# Driver.net
KiCad netlist of a schematic drawn in EAGLE
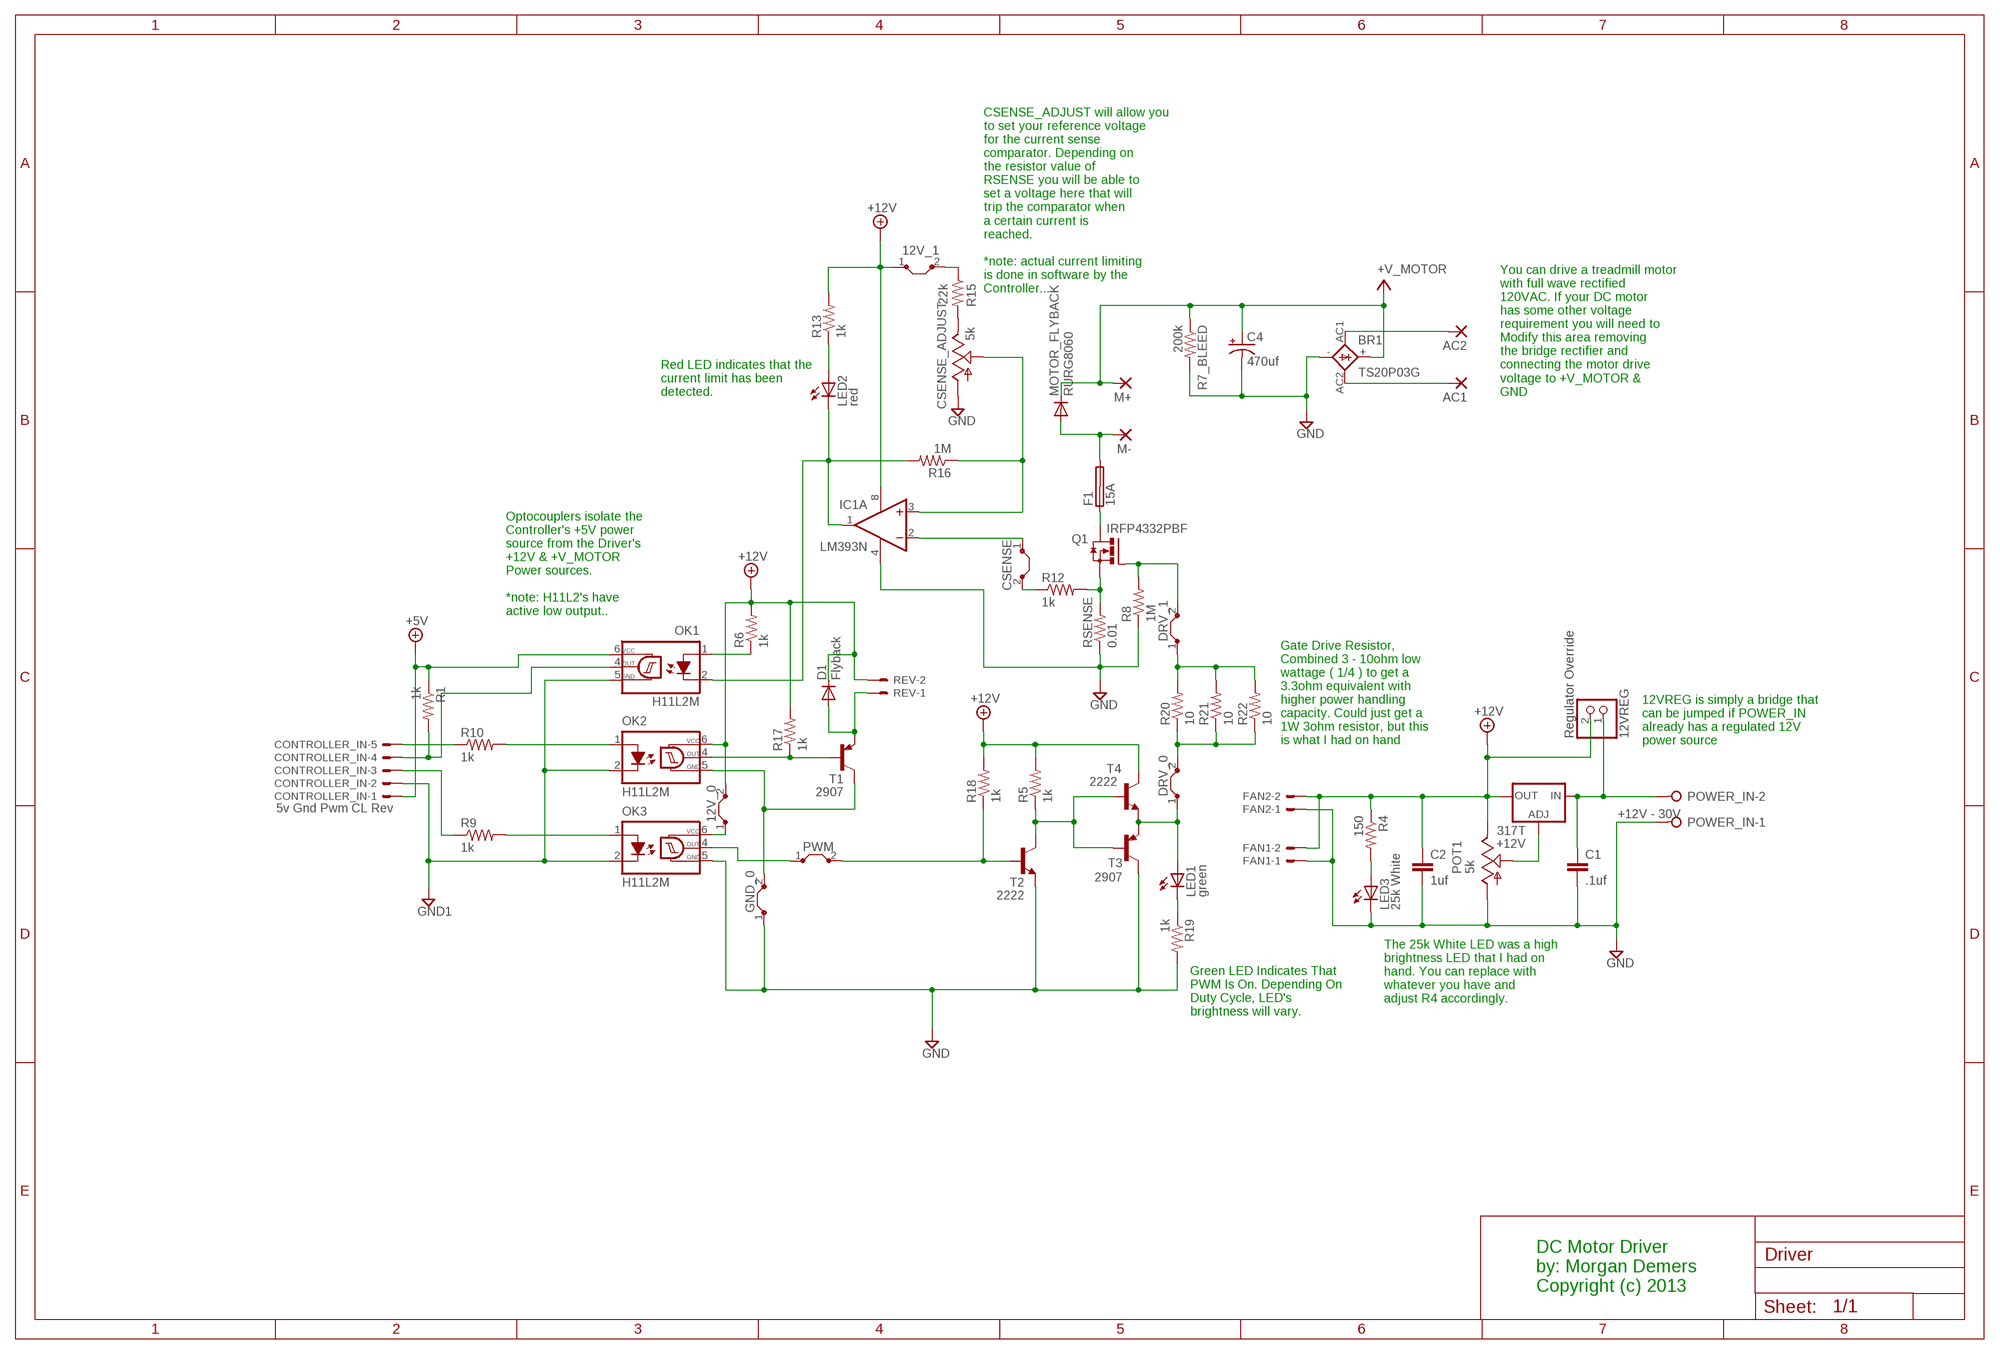
[diagram p0: schematic, sheet 1]

(export (version "E")
  (design (tool "Eeschema 10.0.6"))
  (components
    (comp (ref "12VREG")
      (value "Regulator Override")
      (footprint "eagle-import:1X02")
      (libsource (lib "eagle-import") (part "PINHD-1X2"))
    )
    (comp (ref "12V_0")
      (value "J10MM")
      (footprint "eagle-import:10")
      (libsource (lib "eagle-import") (part "J10MM"))
    )
    (comp (ref "12V_1")
      (value "J5MM")
      (footprint "eagle-import:05")
      (libsource (lib "eagle-import") (part "J5MM"))
    )
    (comp (ref "317T")
      (value "+12V")
      (footprint "eagle-import:317TS")
      (libsource (lib "eagle-import") (part "LM317TS"))
    )
    (comp (ref "AC1")
      (value "WIREPAD4,16O1,6")
      (footprint "eagle-import:4,16O1,6")
      (libsource (lib "eagle-import") (part "WIREPAD4,16O1,6"))
    )
    (comp (ref "AC2")
      (value "WIREPAD4,16O1,6")
      (footprint "eagle-import:4,16O1,6")
      (libsource (lib "eagle-import") (part "WIREPAD4,16O1,6"))
    )
    (comp (ref "BR1")
      (value "TS20P03G")
      (footprint "eagle-import:FB32")
      (libsource (lib "eagle-import") (part "FB32"))
    )
    (comp (ref "C1")
      (value ".1uf")
      (footprint "eagle-import:C2.5-3")
      (libsource (lib "eagle-import") (part "C2,5-3"))
    )
    (comp (ref "C2")
      (value "1uf")
      (footprint "eagle-import:C2.5-3")
      (libsource (lib "eagle-import") (part "C2,5-3"))
    )
    (comp (ref "C4")
      (value "470uf")
      (footprint "eagle-import:EB22,5D")
      (libsource (lib "eagle-import") (part "CPOL-USE10-22.5"))
    )
    (comp (ref "CONTROLLER_IN")
      (value "5v Gnd Pwm CL Rev")
      (footprint "eagle-import:22-23-2051")
      (fields (field (name "MF") "MOLEX") (field (name "MPN") "22-23-2051"))
      (libsource (lib "eagle-import") (part "22-23-2051"))
    )
    (comp (ref "CSENSE")
      (value "J7MM")
      (footprint "eagle-import:07")
      (libsource (lib "eagle-import") (part "J7MM"))
    )
    (comp (ref "CSENSE_ADJUST")
      (value "5k")
      (footprint "eagle-import:B25P")
      (libsource (lib "eagle-import") (part "TRIM_US-B25P"))
    )
    (comp (ref "D1")
      (value "Flyback")
      (footprint "eagle-import:D-2.5")
      (libsource (lib "eagle-import") (part "DIODE-D-2.5"))
    )
    (comp (ref "DRV_0")
      (value "J5MM")
      (footprint "eagle-import:05")
      (libsource (lib "eagle-import") (part "J5MM"))
    )
    (comp (ref "DRV_1")
      (value "J12MM")
      (footprint "eagle-import:12")
      (libsource (lib "eagle-import") (part "J12MM"))
    )
    (comp (ref "F1")
      (value "15A")
      (footprint "eagle-import:SHK20L")
      (libsource (lib "eagle-import") (part "SHK20L"))
    )
    (comp (ref "FAN1")
      (value "22-23-2021")
      (footprint "eagle-import:22-23-2021")
      (fields (field (name "MF") "MOLEX"))
      (libsource (lib "eagle-import") (part "22-23-2021"))
    )
    (comp (ref "FAN2")
      (value "22-23-2021")
      (footprint "eagle-import:22-23-2021")
      (fields (field (name "MF") "MOLEX"))
      (libsource (lib "eagle-import") (part "22-23-2021"))
    )
    (comp (ref "GND_0")
      (value "J7MM")
      (footprint "eagle-import:07")
      (libsource (lib "eagle-import") (part "J7MM"))
    )
    (comp (ref "IC1")
      (value "LM393N")
      (footprint "eagle-import:DIL08")
      (libsource (lib "eagle-import") (part "LM393N"))
    )
    (comp (ref "LED1")
      (value "green")
      (footprint "eagle-import:LED3MM")
      (libsource (lib "eagle-import") (part "LED3MM"))
    )
    (comp (ref "LED2")
      (value "red")
      (footprint "eagle-import:LED3MM")
      (libsource (lib "eagle-import") (part "LED3MM"))
    )
    (comp (ref "LED3")
      (value "25k White")
      (footprint "eagle-import:LED3MM")
      (libsource (lib "eagle-import") (part "LED3MM"))
    )
    (comp (ref "M+")
      (value "WIREPAD4,16O1,6")
      (footprint "eagle-import:4,16O1,6")
      (libsource (lib "eagle-import") (part "WIREPAD4,16O1,6"))
    )
    (comp (ref "M-")
      (value "WIREPAD4,16O1,6")
      (footprint "eagle-import:4,16O1,6")
      (libsource (lib "eagle-import") (part "WIREPAD4,16O1,6"))
    )
    (comp (ref "MOTOR_FLYBACK")
      (value "RURG8060")
      (footprint "eagle-import:TO220ACS")
      (libsource (lib "eagle-import") (part "DIODE-TO220V"))
    )
    (comp (ref "OK1")
      (value "H11L2M")
      (footprint "eagle-import:DIL06")
      (fields (field (name "MF") "FAIRCHILD SEMICONDUCTOR"))
      (libsource (lib "eagle-import") (part "H11LM2"))
    )
    (comp (ref "OK2")
      (value "H11L2M")
      (footprint "eagle-import:DIL06")
      (fields (field (name "MF") "FAIRCHILD SEMICONDUCTOR"))
      (libsource (lib "eagle-import") (part "H11LM2"))
    )
    (comp (ref "OK3")
      (value "H11L2M")
      (footprint "eagle-import:DIL06")
      (fields (field (name "MF") "FAIRCHILD SEMICONDUCTOR"))
      (libsource (lib "eagle-import") (part "H11LM2"))
    )
    (comp (ref "POT1")
      (value "5k")
      (footprint "eagle-import:B25P")
      (libsource (lib "eagle-import") (part "TRIM_US-B25P"))
    )
    (comp (ref "POWER_IN")
      (value "+12V - 30V")
      (footprint "eagle-import:W237-132")
      (libsource (lib "eagle-import") (part "W237-02P"))
    )
    (comp (ref "PWM")
      (value "J5MM")
      (footprint "eagle-import:05")
      (libsource (lib "eagle-import") (part "J5MM"))
    )
    (comp (ref "Q1")
      (value "IRFP4332PBF")
      (footprint "eagle-import:TO247BV")
      (libsource (lib "eagle-import") (part "IRFP240"))
    )
    (comp (ref "R1")
      (value "1k")
      (footprint "eagle-import:0204_7")
      (libsource (lib "eagle-import") (part "R-US_0204/7"))
    )
    (comp (ref "R4")
      (value "150")
      (footprint "eagle-import:0204V")
      (libsource (lib "eagle-import") (part "R-US_0204/2V"))
    )
    (comp (ref "R5")
      (value "1k")
      (footprint "eagle-import:0204V")
      (libsource (lib "eagle-import") (part "R-US_0204/2V"))
    )
    (comp (ref "R6")
      (value "1k")
      (footprint "eagle-import:0204V")
      (libsource (lib "eagle-import") (part "R-US_0204/2V"))
    )
    (comp (ref "R7_BLEED")
      (value "200k")
      (footprint "eagle-import:0207_10")
      (libsource (lib "eagle-import") (part "R-US_0207/10"))
    )
    (comp (ref "R8")
      (value "1M")
      (footprint "eagle-import:0204V")
      (libsource (lib "eagle-import") (part "R-US_0204/2V"))
    )
    (comp (ref "R9")
      (value "1k")
      (footprint "eagle-import:0204V")
      (libsource (lib "eagle-import") (part "R-US_0204/2V"))
    )
    (comp (ref "R10")
      (value "1k")
      (footprint "eagle-import:0204V")
      (libsource (lib "eagle-import") (part "R-US_0204/2V"))
    )
    (comp (ref "R12")
      (value "1k")
      (footprint "eagle-import:0204V")
      (libsource (lib "eagle-import") (part "R-US_0204/2V"))
    )
    (comp (ref "R13")
      (value "1k")
      (footprint "eagle-import:0204V")
      (libsource (lib "eagle-import") (part "R-US_0204/2V"))
    )
    (comp (ref "R15")
      (value "22k")
      (footprint "eagle-import:0204V")
      (libsource (lib "eagle-import") (part "R-US_0204/2V"))
    )
    (comp (ref "R16")
      (value "1M")
      (footprint "eagle-import:0204_5")
      (libsource (lib "eagle-import") (part "R-US_0204/5"))
    )
    (comp (ref "R17")
      (value "1k")
      (footprint "eagle-import:0204_5")
      (libsource (lib "eagle-import") (part "R-US_0204/5"))
    )
    (comp (ref "R18")
      (value "1k")
      (footprint "eagle-import:0204_7")
      (libsource (lib "eagle-import") (part "R-US_0204/7"))
    )
    (comp (ref "R19")
      (value "1k")
      (footprint "eagle-import:0204V")
      (libsource (lib "eagle-import") (part "R-US_0204/2V"))
    )
    (comp (ref "R20")
      (value "10")
      (footprint "eagle-import:0204V")
      (libsource (lib "eagle-import") (part "R-US_0204/2V"))
    )
    (comp (ref "R21")
      (value "10")
      (footprint "eagle-import:0204V")
      (libsource (lib "eagle-import") (part "R-US_0204/2V"))
    )
    (comp (ref "R22")
      (value "10")
      (footprint "eagle-import:0204V")
      (libsource (lib "eagle-import") (part "R-US_0204/2V"))
    )
    (comp (ref "REV")
      (value "22-23-2021")
      (footprint "eagle-import:22-23-2021")
      (fields (field (name "MF") "MOLEX"))
      (libsource (lib "eagle-import") (part "22-23-2021"))
    )
    (comp (ref "RSENSE")
      (value "0.01")
      (footprint "eagle-import:0204V")
      (libsource (lib "eagle-import") (part "R-US_0204/2V"))
    )
    (comp (ref "T1")
      (value "2907")
      (footprint "eagle-import:TO92-CBE")
      (libsource (lib "eagle-import") (part "MPSA56"))
    )
    (comp (ref "T2")
      (value "2222")
      (footprint "eagle-import:TO92-EBC")
      (libsource (lib "eagle-import") (part "-NPN-TO92-EBC"))
    )
    (comp (ref "T3")
      (value "2907")
      (footprint "eagle-import:TO92-CBE")
      (libsource (lib "eagle-import") (part "MPSA56"))
    )
    (comp (ref "T4")
      (value "2222")
      (footprint "eagle-import:TO92-EBC")
      (libsource (lib "eagle-import") (part "-NPN-TO92-EBC"))
    )
  )
  (nets
    (net (code "1") (name "+5V") (class "Default")
      (node (ref "CONTROLLER_IN") (pin "1") (pinfunction "S_1") (pintype "passive"))
      (node (ref "OK1") (pin "6") (pinfunction "VCC_6") (pintype "power_in"))
      (node (ref "R1") (pin "1") (pinfunction "1_1") (pintype "passive"))
    )
    (net (code "2") (name "+12V") (class "Default")
      (node (ref "12VREG") (pin "2") (pinfunction "2_2") (pintype "passive"))
      (node (ref "12V_0") (pin "2") (pinfunction "2_2") (pintype "passive"))
      (node (ref "12V_1") (pin "1") (pinfunction "1_1") (pintype "passive"))
      (node (ref "317T") (pin "2") (pinfunction "OUT_2") (pintype "passive"))
      (node (ref "C2") (pin "1") (pinfunction "1_1") (pintype "passive"))
      (node (ref "D1") (pin "C") (pinfunction "C_C") (pintype "passive"))
      (node (ref "FAN1") (pin "2") (pinfunction "S_2") (pintype "passive"))
      (node (ref "FAN2") (pin "2") (pinfunction "S_2") (pintype "passive"))
      (node (ref "IC1") (pin "8") (pinfunction "V+_8") (pintype "power_in"))
      (node (ref "OK2") (pin "6") (pinfunction "VCC_6") (pintype "power_in"))
      (node (ref "POT1") (pin "E") (pinfunction "E_E") (pintype "passive"))
      (node (ref "R13") (pin "2") (pinfunction "2_2") (pintype "passive"))
      (node (ref "R17") (pin "2") (pinfunction "2_2") (pintype "passive"))
      (node (ref "R18") (pin "2") (pinfunction "2_2") (pintype "passive"))
      (node (ref "R4") (pin "1") (pinfunction "1_1") (pintype "passive"))
      (node (ref "R5") (pin "2") (pinfunction "2_2") (pintype "passive"))
      (node (ref "R6") (pin "2") (pinfunction "2_2") (pintype "passive"))
      (node (ref "REV") (pin "2") (pinfunction "S_2") (pintype "passive"))
      (node (ref "T4") (pin "C") (pinfunction "C_C") (pintype "passive"))
    )
    (net (code "3") (name "+V_MOTOR") (class "Default")
      (node (ref "BR1") (pin "+") (pinfunction "+_+") (pintype "passive"))
      (node (ref "C4") (pin "+") (pinfunction "+_+") (pintype "passive"))
      (node (ref "M+") (pin "1") (pinfunction "P_1") (pintype "passive"))
      (node (ref "MOTOR_FLYBACK") (pin "C") (pinfunction "C_C") (pintype "passive"))
      (node (ref "R7_BLEED") (pin "1") (pinfunction "1_1") (pintype "passive"))
    )
    (net (code "4") (name "GND") (class "Default")
      (node (ref "BR1") (pin "-") (pinfunction "-_-") (pintype "passive"))
      (node (ref "C1") (pin "2") (pinfunction "2_2") (pintype "passive"))
      (node (ref "C2") (pin "2") (pinfunction "2_2") (pintype "passive"))
      (node (ref "C4") (pin "-") (pinfunction "-_-") (pintype "passive"))
      (node (ref "CSENSE_ADJUST") (pin "A") (pinfunction "A_A") (pintype "passive"))
      (node (ref "FAN1") (pin "1") (pinfunction "S_1") (pintype "passive"))
      (node (ref "FAN2") (pin "1") (pinfunction "S_1") (pintype "passive"))
      (node (ref "GND_0") (pin "1") (pinfunction "1_1") (pintype "passive"))
      (node (ref "IC1") (pin "4") (pinfunction "V-_4") (pintype "power_in"))
      (node (ref "LED3") (pin "K") (pinfunction "C_K") (pintype "passive"))
      (node (ref "OK3") (pin "5") (pinfunction "GND_5") (pintype "power_in"))
      (node (ref "POT1") (pin "A") (pinfunction "A_A") (pintype "passive"))
      (node (ref "POWER_IN") (pin "1") (pinfunction "KL_1") (pintype "passive"))
      (node (ref "R19") (pin "2") (pinfunction "2_2") (pintype "passive"))
      (node (ref "R7_BLEED") (pin "2") (pinfunction "2_2") (pintype "passive"))
      (node (ref "R8") (pin "1") (pinfunction "1_1") (pintype "passive"))
      (node (ref "RSENSE") (pin "1") (pinfunction "1_1") (pintype "passive"))
      (node (ref "T2") (pin "E") (pinfunction "E_E") (pintype "passive"))
      (node (ref "T3") (pin "C") (pinfunction "C_C") (pintype "passive"))
    )
    (net (code "5") (name "GND1") (class "Default")
      (node (ref "CONTROLLER_IN") (pin "2") (pinfunction "S_2") (pintype "passive"))
      (node (ref "OK1") (pin "5") (pinfunction "GND_5") (pintype "power_in"))
      (node (ref "OK2") (pin "2") (pinfunction "C_2") (pintype "passive"))
      (node (ref "OK3") (pin "2") (pinfunction "C_2") (pintype "passive"))
    )
    (net (code "6") (name "Net-(12V_1-Pad2)") (class "Default")
      (node (ref "12V_1") (pin "2") (pinfunction "2_2") (pintype "passive"))
      (node (ref "R15") (pin "1") (pinfunction "1_1") (pintype "passive"))
    )
    (net (code "7") (name "Net-(317T-ADJ)") (class "Default")
      (node (ref "317T") (pin "1") (pinfunction "ADJ_1") (pintype "input"))
      (node (ref "POT1") (pin "S") (pinfunction "S_S") (pintype "passive"))
    )
    (net (code "8") (name "Net-(317T-IN)") (class "Default")
      (node (ref "12VREG") (pin "1") (pinfunction "1_1") (pintype "passive"))
      (node (ref "317T") (pin "3") (pinfunction "IN_3") (pintype "input"))
      (node (ref "C1") (pin "1") (pinfunction "1_1") (pintype "passive"))
      (node (ref "POWER_IN") (pin "2") (pinfunction "KL_2") (pintype "passive"))
    )
    (net (code "9") (name "Net-(AC1-P)") (class "Default")
      (node (ref "AC1") (pin "1") (pinfunction "P_1") (pintype "passive"))
      (node (ref "BR1") (pin "AC2") (pinfunction "AC2_AC2") (pintype "passive"))
    )
    (net (code "10") (name "Net-(AC2-P)") (class "Default")
      (node (ref "AC2") (pin "1") (pinfunction "P_1") (pintype "passive"))
      (node (ref "BR1") (pin "AC1") (pinfunction "AC1_AC1") (pintype "passive"))
    )
    (net (code "11") (name "Net-(CONTROLLER_INC-S)") (class "Default")
      (node (ref "CONTROLLER_IN") (pin "3") (pinfunction "S_3") (pintype "passive"))
      (node (ref "R9") (pin "1") (pinfunction "1_1") (pintype "passive"))
    )
    (net (code "12") (name "Net-(CONTROLLER_IND-S)") (class "Default")
      (node (ref "CONTROLLER_IN") (pin "4") (pinfunction "S_4") (pintype "passive"))
      (node (ref "OK1") (pin "4") (pinfunction "OUT_4") (pintype "output"))
      (node (ref "R1") (pin "2") (pinfunction "2_2") (pintype "passive"))
    )
    (net (code "13") (name "Net-(CONTROLLER_INE-S)") (class "Default")
      (node (ref "CONTROLLER_IN") (pin "5") (pinfunction "S_5") (pintype "passive"))
      (node (ref "R10") (pin "1") (pinfunction "1_1") (pintype "passive"))
    )
    (net (code "14") (name "Net-(CSENSE-Pad2)") (class "Default")
      (node (ref "CSENSE") (pin "2") (pinfunction "2_2") (pintype "passive"))
      (node (ref "R12") (pin "1") (pinfunction "1_1") (pintype "passive"))
    )
    (net (code "15") (name "Net-(CSENSE_ADJUST-PadE)") (class "Default")
      (node (ref "CSENSE_ADJUST") (pin "E") (pinfunction "E_E") (pintype "passive"))
      (node (ref "R15") (pin "2") (pinfunction "2_2") (pintype "passive"))
    )
    (net (code "16") (name "Net-(DRV_0-Pad1)") (class "Default")
      (node (ref "DRV_0") (pin "1") (pinfunction "1_1") (pintype "passive"))
      (node (ref "LED1") (pin "A") (pinfunction "A_A") (pintype "passive"))
      (node (ref "T3") (pin "E") (pinfunction "E_E") (pintype "passive"))
      (node (ref "T4") (pin "E") (pinfunction "E_E") (pintype "passive"))
    )
    (net (code "17") (name "Net-(DRV_0-Pad2)") (class "Default")
      (node (ref "DRV_0") (pin "2") (pinfunction "2_2") (pintype "passive"))
      (node (ref "R20") (pin "1") (pinfunction "1_1") (pintype "passive"))
      (node (ref "R21") (pin "1") (pinfunction "1_1") (pintype "passive"))
      (node (ref "R22") (pin "1") (pinfunction "1_1") (pintype "passive"))
    )
    (net (code "18") (name "Net-(DRV_1-Pad1)") (class "Default")
      (node (ref "DRV_1") (pin "1") (pinfunction "1_1") (pintype "passive"))
      (node (ref "R20") (pin "2") (pinfunction "2_2") (pintype "passive"))
      (node (ref "R21") (pin "2") (pinfunction "2_2") (pintype "passive"))
      (node (ref "R22") (pin "2") (pinfunction "2_2") (pintype "passive"))
    )
    (net (code "19") (name "Net-(DRV_1-Pad2)") (class "Default")
      (node (ref "DRV_1") (pin "2") (pinfunction "2_2") (pintype "passive"))
      (node (ref "Q1") (pin "G") (pinfunction "G_G") (pintype "passive"))
      (node (ref "R8") (pin "2") (pinfunction "2_2") (pintype "passive"))
    )
    (net (code "20") (name "Net-(F1-Pad1A)") (class "Default")
      (node (ref "F1") (pin "1A") (pinfunction "1A_1A") (pintype "passive"))
      (node (ref "Q1") (pin "D") (pinfunction "D_D") (pintype "passive"))
    )
    (net (code "21") (name "Net-(IC1A-+IN)") (class "Default")
      (node (ref "CSENSE_ADJUST") (pin "S") (pinfunction "S_S") (pintype "passive"))
      (node (ref "IC1") (pin "3") (pinfunction "+IN_3") (pintype "input"))
      (node (ref "R16") (pin "1") (pinfunction "1_1") (pintype "passive"))
    )
    (net (code "22") (name "Net-(IC1A--IN)") (class "Default")
      (node (ref "CSENSE") (pin "1") (pinfunction "1_1") (pintype "passive"))
      (node (ref "IC1") (pin "2") (pinfunction "-IN_2") (pintype "input"))
    )
    (net (code "23") (name "Net-(IC1A-OUT)") (class "Default")
      (node (ref "IC1") (pin "1") (pinfunction "OUT_1") (pintype "output"))
      (node (ref "LED2") (pin "K") (pinfunction "C_K") (pintype "passive"))
      (node (ref "OK1") (pin "2") (pinfunction "C_2") (pintype "passive"))
      (node (ref "R16") (pin "2") (pinfunction "2_2") (pintype "passive"))
    )
    (net (code "24") (name "Net-(LED1-C)") (class "Default")
      (node (ref "LED1") (pin "K") (pinfunction "C_K") (pintype "passive"))
      (node (ref "R19") (pin "1") (pinfunction "1_1") (pintype "passive"))
    )
    (net (code "25") (name "Net-(LED2-PadA)") (class "Default")
      (node (ref "LED2") (pin "A") (pinfunction "A_A") (pintype "passive"))
      (node (ref "R13") (pin "1") (pinfunction "1_1") (pintype "passive"))
    )
    (net (code "26") (name "Net-(LED3-PadA)") (class "Default")
      (node (ref "LED3") (pin "A") (pinfunction "A_A") (pintype "passive"))
      (node (ref "R4") (pin "2") (pinfunction "2_2") (pintype "passive"))
    )
    (net (code "27") (name "Net-(M--P)") (class "Default")
      (node (ref "F1") (pin "2A") (pinfunction "2A_2A") (pintype "passive"))
      (node (ref "M-") (pin "1") (pinfunction "P_1") (pintype "passive"))
      (node (ref "MOTOR_FLYBACK") (pin "A") (pinfunction "A_A") (pintype "passive"))
    )
    (net (code "28") (name "Net-(OK1-A)") (class "Default")
      (node (ref "OK1") (pin "1") (pinfunction "A_1") (pintype "passive"))
      (node (ref "R6") (pin "1") (pinfunction "1_1") (pintype "passive"))
    )
    (net (code "29") (name "Net-(OK2-A)") (class "Default")
      (node (ref "OK2") (pin "1") (pinfunction "A_1") (pintype "passive"))
      (node (ref "R10") (pin "2") (pinfunction "2_2") (pintype "passive"))
    )
    (net (code "30") (name "Net-(OK2-GND)") (class "Default")
      (node (ref "GND_0") (pin "2") (pinfunction "2_2") (pintype "passive"))
      (node (ref "OK2") (pin "5") (pinfunction "GND_5") (pintype "power_in"))
      (node (ref "T1") (pin "C") (pinfunction "C_C") (pintype "passive"))
    )
    (net (code "31") (name "Net-(OK2-OUT)") (class "Default")
      (node (ref "OK2") (pin "4") (pinfunction "OUT_4") (pintype "output"))
      (node (ref "R17") (pin "1") (pinfunction "1_1") (pintype "passive"))
      (node (ref "T1") (pin "B") (pinfunction "B_B") (pintype "passive"))
    )
    (net (code "32") (name "Net-(OK3-A)") (class "Default")
      (node (ref "OK3") (pin "1") (pinfunction "A_1") (pintype "passive"))
      (node (ref "R9") (pin "2") (pinfunction "2_2") (pintype "passive"))
    )
    (net (code "33") (name "Net-(OK3-OUT)") (class "Default")
      (node (ref "OK3") (pin "4") (pinfunction "OUT_4") (pintype "output"))
      (node (ref "PWM") (pin "1") (pinfunction "1_1") (pintype "passive"))
    )
    (net (code "34") (name "Net-(OK3-VCC)") (class "Default")
      (node (ref "12V_0") (pin "1") (pinfunction "1_1") (pintype "passive"))
      (node (ref "OK3") (pin "6") (pinfunction "VCC_6") (pintype "power_in"))
    )
    (net (code "35") (name "Net-(PWM-Pad2)") (class "Default")
      (node (ref "PWM") (pin "2") (pinfunction "2_2") (pintype "passive"))
      (node (ref "R18") (pin "1") (pinfunction "1_1") (pintype "passive"))
      (node (ref "T2") (pin "B") (pinfunction "B_B") (pintype "passive"))
    )
    (net (code "36") (name "Net-(Q1-PadS)") (class "Default")
      (node (ref "Q1") (pin "S") (pinfunction "S_S") (pintype "passive"))
      (node (ref "R12") (pin "2") (pinfunction "2_2") (pintype "passive"))
      (node (ref "RSENSE") (pin "2") (pinfunction "2_2") (pintype "passive"))
    )
    (net (code "37") (name "Net-(R5-Pad1)") (class "Default")
      (node (ref "R5") (pin "1") (pinfunction "1_1") (pintype "passive"))
      (node (ref "T2") (pin "C") (pinfunction "C_C") (pintype "passive"))
      (node (ref "T3") (pin "B") (pinfunction "B_B") (pintype "passive"))
      (node (ref "T4") (pin "B") (pinfunction "B_B") (pintype "passive"))
    )
    (net (code "38") (name "Net-(REVA-S)") (class "Default")
      (node (ref "D1") (pin "A") (pinfunction "A_A") (pintype "passive"))
      (node (ref "REV") (pin "1") (pinfunction "S_1") (pintype "passive"))
      (node (ref "T1") (pin "E") (pinfunction "E_E") (pintype "passive"))
    )
    (net (code "39") (name "unconnected-(F1-Pad1B)") (class "Default")
      (node (ref "F1") (pin "1B") (pinfunction "1B_1B") (pintype "passive"))
    )
    (net (code "40") (name "unconnected-(F1-Pad2B)") (class "Default")
      (node (ref "F1") (pin "2B") (pinfunction "2B_2B") (pintype "passive"))
    )
  )
)
